# stm32f103core.net
KiCad netlist of a schematic drawn in Altium Designer
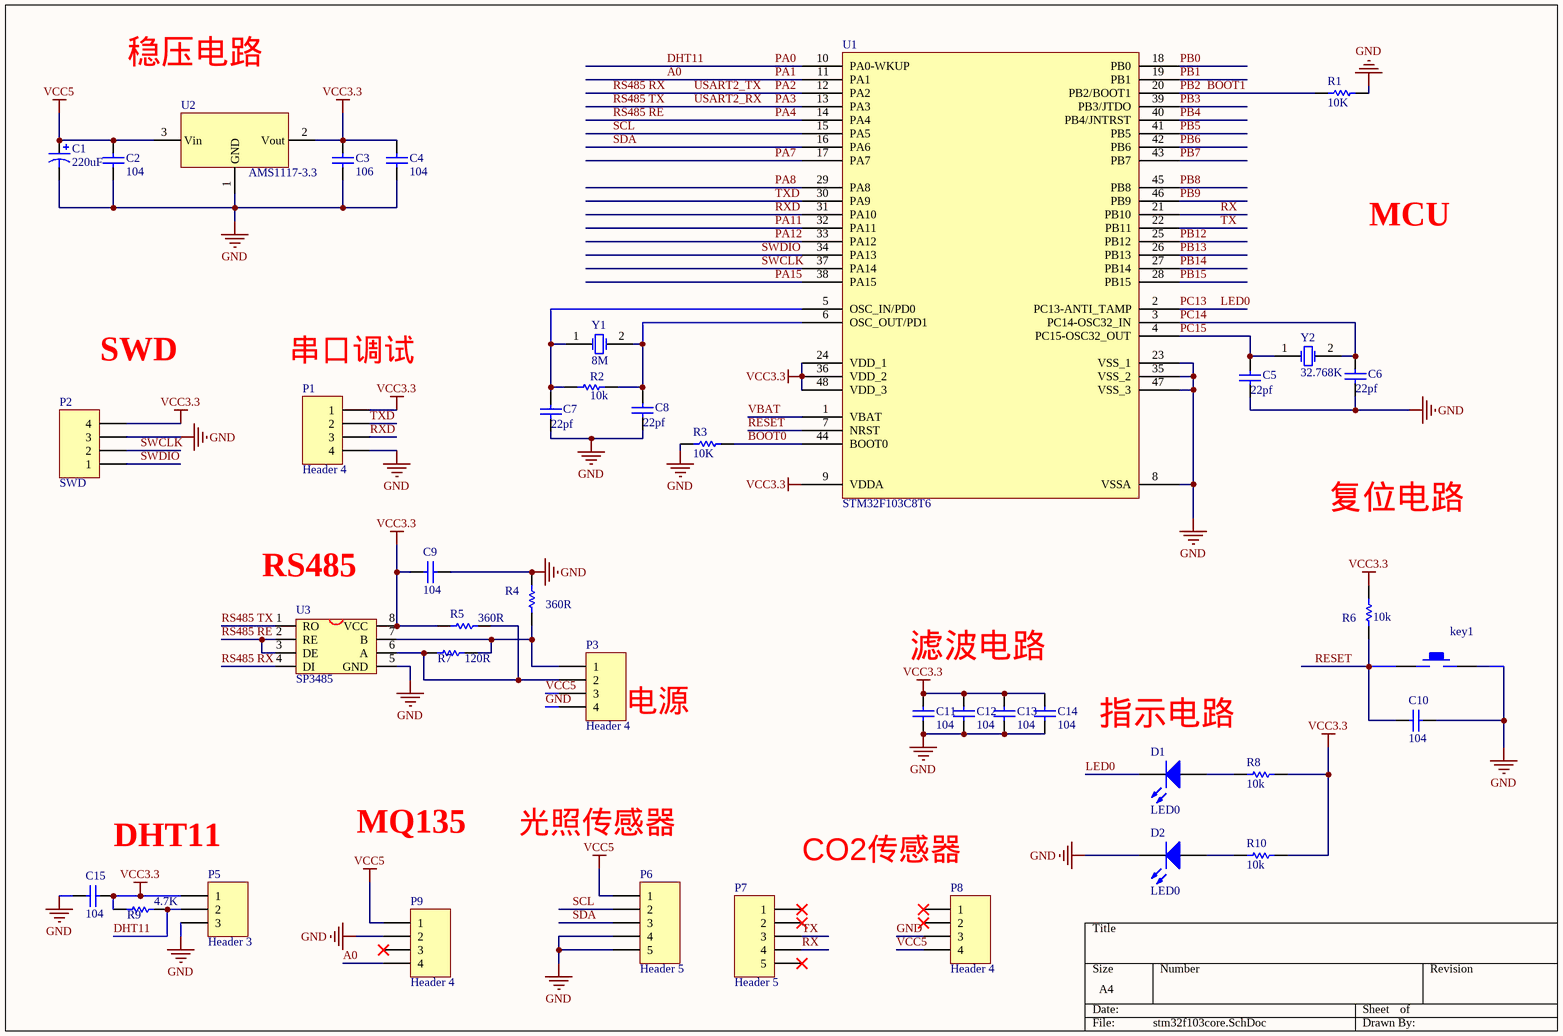
[diagram p0: stm32f103core.SchDoc]

(export (version "E")
  (design (tool "Eeschema 10.0.6"))
  (components
    (comp (ref "C1")
      (value "220uF")
      (footprint "CC6.56.5")
      (description "极性电容")
      (fields (field (name "PUBLISHER") "Altium Limited"))
      (libsource (lib "stm32f103core") (part "Cap Pol2"))
    )
    (comp (ref "C2")
      (value "104")
      (footprint "0603p")
      (description "Capacitor")
      (fields (field (name "PUBLISHER") "Altium Limited"))
      (libsource (lib "stm32f103core") (part "C"))
    )
    (comp (ref "C3")
      (value "106")
      (footprint "0603p")
      (description "Capacitor")
      (fields (field (name "PUBLISHER") "Altium Limited"))
      (libsource (lib "stm32f103core") (part "C"))
    )
    (comp (ref "C4")
      (value "104")
      (footprint "0603p")
      (description "Capacitor")
      (fields (field (name "PUBLISHER") "Altium Limited"))
      (libsource (lib "stm32f103core") (part "C"))
    )
    (comp (ref "C5")
      (value "22pf")
      (footprint "0603p")
      (description "Capacitor")
      (fields (field (name "PUBLISHER") "Altium Limited"))
      (libsource (lib "stm32f103core") (part "C"))
    )
    (comp (ref "C6")
      (value "22pf")
      (footprint "0603p")
      (description "Capacitor")
      (fields (field (name "PUBLISHER") "Altium Limited"))
      (libsource (lib "stm32f103core") (part "C"))
    )
    (comp (ref "C7")
      (value "22pf")
      (footprint "0603p")
      (description "Capacitor")
      (fields (field (name "PUBLISHER") "Altium Limited"))
      (libsource (lib "stm32f103core") (part "C"))
    )
    (comp (ref "C8")
      (value "22pf")
      (footprint "0603p")
      (description "Capacitor")
      (fields (field (name "PUBLISHER") "Altium Limited"))
      (libsource (lib "stm32f103core") (part "C"))
    )
    (comp (ref "C9")
      (value "104")
      (footprint "0603P")
      (description "Capacitor")
      (fields (field (name "PUBLISHER") "Altium Limited"))
      (libsource (lib "stm32f103core") (part "C"))
    )
    (comp (ref "C10")
      (value "104")
      (footprint "0603p")
      (description "Capacitor")
      (fields (field (name "PUBLISHER") "Altium Limited"))
      (libsource (lib "stm32f103core") (part "C"))
    )
    (comp (ref "C11")
      (value "104")
      (footprint "0603p")
      (description "Capacitor")
      (fields (field (name "PUBLISHER") "Altium Limited"))
      (libsource (lib "stm32f103core") (part "C"))
    )
    (comp (ref "C12")
      (value "104")
      (footprint "0603p")
      (description "Capacitor")
      (fields (field (name "PUBLISHER") "Altium Limited"))
      (libsource (lib "stm32f103core") (part "C"))
    )
    (comp (ref "C13")
      (value "104")
      (footprint "0603p")
      (description "Capacitor")
      (fields (field (name "PUBLISHER") "Altium Limited"))
      (libsource (lib "stm32f103core") (part "C"))
    )
    (comp (ref "C14")
      (value "104")
      (footprint "0603p")
      (description "Capacitor")
      (fields (field (name "PUBLISHER") "Altium Limited"))
      (libsource (lib "stm32f103core") (part "C"))
    )
    (comp (ref "C15")
      (value "104")
      (footprint "0603p")
      (description "Capacitor")
      (fields (field (name "PUBLISHER") "Altium Limited"))
      (libsource (lib "stm32f103core") (part "C"))
    )
    (comp (ref "D1")
      (value "LED0")
      (footprint "LED0805")
      (description "Typical INFRARED GaAs LED")
      (fields (field (name "PUBLISHER") "Altium Limited"))
      (libsource (lib "stm32f103core") (part "LED0"))
    )
    (comp (ref "D2")
      (value "LED0")
      (footprint "LED0805")
      (description "Typical INFRARED GaAs LED")
      (fields (field (name "PUBLISHER") "Altium Limited"))
      (libsource (lib "stm32f103core") (part "LED0"))
    )
    (comp (ref "key1") (value "Key") (footprint "Key") (libsource (lib "stm32f103core") (part "Key")))
    (comp (ref "P1")
      (value "Header 4")
      (footprint "HDR1X4")
      (description "Header, 4-Pin")
      (fields (field (name "PUBLISHER") "Altium Limited"))
      (libsource (lib "") (part "Header 4_2"))
    )
    (comp (ref "P2")
      (value "SWD")
      (footprint "HDR1X4")
      (description "Header, 4-Pin")
      (fields (field (name "PUBLISHER") "Altium Limited"))
      (libsource (lib "") (part "Header 4_1"))
    )
    (comp (ref "P3")
      (value "Header 4")
      (footprint "HDR1X4")
      (description "Header, 4-Pin")
      (fields (field (name "PUBLISHER") "Altium Limited"))
      (libsource (lib "Miscellaneous Connectors") (part "Header 4"))
    )
    (comp (ref "P5")
      (value "Header 3")
      (footprint "HDR1X3")
      (description "Header, 3-Pin")
      (fields (field (name "PUBLISHER") "Altium Limited"))
      (libsource (lib "Miscellaneous Connectors") (part "Header 3"))
    )
    (comp (ref "P6")
      (value "Header 5")
      (footprint "HDR1X5")
      (description "Header, 5-Pin")
      (fields (field (name "PUBLISHER") "Altium Limited"))
      (libsource (lib "Miscellaneous Connectors") (part "Header 5"))
    )
    (comp (ref "P7")
      (value "Header 5")
      (footprint "HDR1X5")
      (description "Header, 5-Pin")
      (fields (field (name "PUBLISHER") "Altium Limited"))
      (libsource (lib "") (part "Header 5_1"))
    )
    (comp (ref "P8")
      (value "Header 4")
      (footprint "HDR1X4")
      (description "Header, 4-Pin")
      (fields (field (name "PUBLISHER") "Altium Limited"))
      (libsource (lib "Miscellaneous Connectors") (part "Header 4"))
    )
    (comp (ref "P9")
      (value "Header 4")
      (footprint "HDR1X4")
      (description "Header, 4-Pin")
      (fields (field (name "PUBLISHER") "Altium Limited"))
      (libsource (lib "Miscellaneous Connectors") (part "Header 4"))
    )
    (comp (ref "R1")
      (value "10K")
      (footprint "0603p")
      (description "Resistor")
      (fields (field (name "PUBLISHER") "Altium Limited"))
      (libsource (lib "stm32f103core") (part "R"))
    )
    (comp (ref "R2")
      (value "10k")
      (footprint "0603p")
      (description "Resistor")
      (fields (field (name "PUBLISHER") "Altium Limited"))
      (libsource (lib "stm32f103core") (part "R"))
    )
    (comp (ref "R3")
      (value "10K")
      (footprint "0603p")
      (description "Resistor")
      (fields (field (name "PUBLISHER") "Altium Limited"))
      (libsource (lib "stm32f103core") (part "R"))
    )
    (comp (ref "R4")
      (value "360R")
      (footprint "0603p")
      (description "Resistor")
      (fields (field (name "PUBLISHER") "Altium Limited"))
      (libsource (lib "stm32f103core") (part "R"))
    )
    (comp (ref "R5")
      (value "360R")
      (footprint "0603p")
      (description "Resistor")
      (fields (field (name "PUBLISHER") "Altium Limited"))
      (libsource (lib "stm32f103core") (part "R"))
    )
    (comp (ref "R6")
      (value "10k")
      (footprint "0603p")
      (description "Resistor")
      (fields (field (name "PUBLISHER") "Altium Limited"))
      (libsource (lib "stm32f103core") (part "R"))
    )
    (comp (ref "R7")
      (value "120R")
      (footprint "0603p")
      (description "Resistor")
      (fields (field (name "PUBLISHER") "Altium Limited"))
      (libsource (lib "stm32f103core") (part "R"))
    )
    (comp (ref "R8")
      (value "10k")
      (footprint "0603p")
      (description "Resistor")
      (fields (field (name "PUBLISHER") "Altium Limited"))
      (libsource (lib "stm32f103core") (part "R"))
    )
    (comp (ref "R9")
      (value "4.7K")
      (footprint "0603p")
      (description "Resistor")
      (fields (field (name "PUBLISHER") "Altium Limited"))
      (libsource (lib "stm32f103core") (part "R"))
    )
    (comp (ref "R10")
      (value "10k")
      (footprint "0603p")
      (description "Resistor")
      (fields (field (name "PUBLISHER") "Altium Limited"))
      (libsource (lib "stm32f103core") (part "R"))
    )
    (comp (ref "U1")
      (value "STM32F103C8T6")
      (footprint "LQFP48")
      (libsource (lib "stm32f103core") (part "STM32F103C8T6"))
    )
    (comp (ref "U2")
      (value "AMS1117-3.3")
      (footprint "AMS1117")
      (libsource (lib "stm32f103core") (part "AMS1117"))
    )
    (comp (ref "U3")
      (value "SP3485")
      (footprint "SOP-8")
      (libsource (lib "WarShip V3 STM32103封装库") (part "MAX3485"))
    )
    (comp (ref "Y1")
      (value "8M")
      (footprint "49SMD")
      (description "Crystal Oscillator")
      (fields (field (name "PUBLISHER") "Altium Limited"))
      (libsource (lib "stm32f103core") (part "XTAL"))
    )
    (comp (ref "Y2")
      (value "32.768K")
      (footprint "XTAL32")
      (description "Crystal Oscillator")
      (fields (field (name "PUBLISHER") "Altium Limited"))
      (libsource (lib "stm32f103core") (part "XTAL"))
    )
  )
  (nets
    (net (code "1") (name "/A0") (class "Default")
      (node (ref "P9") (pin "4") (pinfunction "4_4") (pintype "passive"))
      (node (ref "U1") (pin "11") (pinfunction "PA1_11") (pintype "passive"))
    )
    (net (code "2") (name "/BOOT0") (class "Default")
      (node (ref "R3") (pin "2") (pinfunction "2_2") (pintype "passive"))
      (node (ref "U1") (pin "44") (pinfunction "BOOT0_44") (pintype "passive"))
    )
    (net (code "3") (name "/BOOT1") (class "Default")
      (node (ref "R1") (pin "2") (pinfunction "2_2") (pintype "passive"))
      (node (ref "U1") (pin "20") (pinfunction "PB2/BOOT1_20") (pintype "passive"))
    )
    (net (code "4") (name "/DHT11") (class "Default")
      (node (ref "P5") (pin "2") (pinfunction "2_2") (pintype "passive"))
      (node (ref "R9") (pin "2") (pinfunction "2_2") (pintype "passive"))
      (node (ref "U1") (pin "10") (pinfunction "PA0-WKUP_10") (pintype "passive"))
    )
    (net (code "5") (name "/LED0") (class "Default")
      (node (ref "D1") (pin "2") (pinfunction "K_2") (pintype "passive"))
      (node (ref "U1") (pin "2") (pinfunction "PC13-ANTI_TAMP_2") (pintype "passive"))
    )
    (net (code "6") (name "/PA2") (class "Default")
      (node (ref "U1") (pin "12") (pinfunction "PA2_12") (pintype "passive"))
      (node (ref "U3") (pin "4") (pinfunction "DI_4") (pintype "passive"))
    )
    (net (code "7") (name "/PA3") (class "Default")
      (node (ref "U1") (pin "13") (pinfunction "PA3_13") (pintype "passive"))
      (node (ref "U3") (pin "1") (pinfunction "RO_1") (pintype "passive"))
    )
    (net (code "8") (name "/PA4") (class "Default")
      (node (ref "U1") (pin "14") (pinfunction "PA4_14") (pintype "passive"))
      (node (ref "U3") (pin "2") (pinfunction "RE_2") (pintype "passive"))
      (node (ref "U3") (pin "3") (pinfunction "DE_3") (pintype "passive"))
    )
    (net (code "9") (name "/PA7") (class "Default")
      (node (ref "U1") (pin "17") (pinfunction "PA7_17") (pintype "passive"))
    )
    (net (code "10") (name "/PA8") (class "Default")
      (node (ref "U1") (pin "29") (pinfunction "PA8_29") (pintype "passive"))
    )
    (net (code "11") (name "/PA11") (class "Default")
      (node (ref "U1") (pin "32") (pinfunction "PA11_32") (pintype "passive"))
    )
    (net (code "12") (name "/PA12") (class "Default")
      (node (ref "U1") (pin "33") (pinfunction "PA12_33") (pintype "passive"))
    )
    (net (code "13") (name "/PA15") (class "Default")
      (node (ref "U1") (pin "38") (pinfunction "PA15_38") (pintype "passive"))
    )
    (net (code "14") (name "/PB0") (class "Default")
      (node (ref "U1") (pin "18") (pinfunction "PB0_18") (pintype "passive"))
    )
    (net (code "15") (name "/PB1") (class "Default")
      (node (ref "U1") (pin "19") (pinfunction "PB1_19") (pintype "passive"))
    )
    (net (code "16") (name "/PB3") (class "Default")
      (node (ref "U1") (pin "39") (pinfunction "PB3/JTDO_39") (pintype "passive"))
    )
    (net (code "17") (name "/PB4") (class "Default")
      (node (ref "U1") (pin "40") (pinfunction "PB4/JNTRST_40") (pintype "passive"))
    )
    (net (code "18") (name "/PB5") (class "Default")
      (node (ref "U1") (pin "41") (pinfunction "PB5_41") (pintype "passive"))
    )
    (net (code "19") (name "/PB6") (class "Default")
      (node (ref "U1") (pin "42") (pinfunction "PB6_42") (pintype "passive"))
    )
    (net (code "20") (name "/PB7") (class "Default")
      (node (ref "U1") (pin "43") (pinfunction "PB7_43") (pintype "passive"))
    )
    (net (code "21") (name "/PB8") (class "Default")
      (node (ref "U1") (pin "45") (pinfunction "PB8_45") (pintype "passive"))
    )
    (net (code "22") (name "/PB9") (class "Default")
      (node (ref "U1") (pin "46") (pinfunction "PB9_46") (pintype "passive"))
    )
    (net (code "23") (name "/PB12") (class "Default")
      (node (ref "U1") (pin "25") (pinfunction "PB12_25") (pintype "passive"))
    )
    (net (code "24") (name "/PB13") (class "Default")
      (node (ref "U1") (pin "26") (pinfunction "PB13_26") (pintype "passive"))
    )
    (net (code "25") (name "/PB14") (class "Default")
      (node (ref "U1") (pin "27") (pinfunction "PB14_27") (pintype "passive"))
    )
    (net (code "26") (name "/PB15") (class "Default")
      (node (ref "U1") (pin "28") (pinfunction "PB15_28") (pintype "passive"))
    )
    (net (code "27") (name "/PC14") (class "Default")
      (node (ref "C6") (pin "2") (pinfunction "2_2") (pintype "passive"))
      (node (ref "U1") (pin "3") (pinfunction "PC14-OSC32_IN_3") (pintype "passive"))
      (node (ref "Y2") (pin "2") (pinfunction "OSC2_2") (pintype "passive"))
    )
    (net (code "28") (name "/PC15") (class "Default")
      (node (ref "C5") (pin "2") (pinfunction "2_2") (pintype "passive"))
      (node (ref "U1") (pin "4") (pinfunction "PC15-OSC32_OUT_4") (pintype "passive"))
      (node (ref "Y2") (pin "1") (pinfunction "OSC1_1") (pintype "passive"))
    )
    (net (code "29") (name "/RESET") (class "Default")
      (node (ref "C10") (pin "1") (pinfunction "1_1") (pintype "passive"))
      (node (ref "R6") (pin "1") (pinfunction "1_1") (pintype "passive"))
      (node (ref "U1") (pin "7") (pinfunction "NRST_7") (pintype "passive"))
      (node (ref "key1") (pin "1") (pinfunction "1_1") (pintype "passive"))
    )
    (net (code "30") (name "/RX") (class "Default")
      (node (ref "P7") (pin "4") (pinfunction "4_4") (pintype "passive"))
      (node (ref "U1") (pin "21") (pinfunction "PB10_21") (pintype "passive"))
    )
    (net (code "31") (name "/RXD") (class "Default")
      (node (ref "P1") (pin "3") (pinfunction "3_3") (pintype "passive"))
      (node (ref "U1") (pin "31") (pinfunction "PA10_31") (pintype "passive"))
    )
    (net (code "32") (name "/SCL") (class "Default")
      (node (ref "P6") (pin "2") (pinfunction "2_2") (pintype "passive"))
      (node (ref "U1") (pin "15") (pinfunction "PA5_15") (pintype "passive"))
    )
    (net (code "33") (name "/SDA") (class "Default")
      (node (ref "P6") (pin "3") (pinfunction "3_3") (pintype "passive"))
      (node (ref "U1") (pin "16") (pinfunction "PA6_16") (pintype "passive"))
    )
    (net (code "34") (name "/SWCLK") (class "Default")
      (node (ref "P2") (pin "2") (pinfunction "2_2") (pintype "passive"))
      (node (ref "U1") (pin "37") (pinfunction "PA14_37") (pintype "passive"))
    )
    (net (code "35") (name "/SWDIO") (class "Default")
      (node (ref "P2") (pin "1") (pinfunction "1_1") (pintype "passive"))
      (node (ref "U1") (pin "34") (pinfunction "PA13_34") (pintype "passive"))
    )
    (net (code "36") (name "/TX") (class "Default")
      (node (ref "P7") (pin "3") (pinfunction "3_3") (pintype "passive"))
      (node (ref "U1") (pin "22") (pinfunction "PB11_22") (pintype "passive"))
    )
    (net (code "37") (name "/TXD") (class "Default")
      (node (ref "P1") (pin "2") (pinfunction "2_2") (pintype "passive"))
      (node (ref "U1") (pin "30") (pinfunction "PA9_30") (pintype "passive"))
    )
    (net (code "38") (name "/VBAT") (class "Default")
      (node (ref "U1") (pin "1") (pinfunction "VBAT_1") (pintype "passive"))
    )
    (net (code "39") (name "GND") (class "Default")
      (node (ref "C1") (pin "2") (pinfunction "2_2") (pintype "passive"))
      (node (ref "C10") (pin "2") (pinfunction "2_2") (pintype "passive"))
      (node (ref "C11") (pin "1") (pinfunction "1_1") (pintype "passive"))
      (node (ref "C12") (pin "1") (pinfunction "1_1") (pintype "passive"))
      (node (ref "C13") (pin "1") (pinfunction "1_1") (pintype "passive"))
      (node (ref "C14") (pin "1") (pinfunction "1_1") (pintype "passive"))
      (node (ref "C15") (pin "1") (pinfunction "1_1") (pintype "passive"))
      (node (ref "C2") (pin "1") (pinfunction "1_1") (pintype "passive"))
      (node (ref "C3") (pin "1") (pinfunction "1_1") (pintype "passive"))
      (node (ref "C4") (pin "1") (pinfunction "1_1") (pintype "passive"))
      (node (ref "C5") (pin "1") (pinfunction "1_1") (pintype "passive"))
      (node (ref "C6") (pin "1") (pinfunction "1_1") (pintype "passive"))
      (node (ref "C7") (pin "1") (pinfunction "1_1") (pintype "passive"))
      (node (ref "C8") (pin "1") (pinfunction "1_1") (pintype "passive"))
      (node (ref "C9") (pin "2") (pinfunction "2_2") (pintype "passive"))
      (node (ref "D2") (pin "2") (pinfunction "K_2") (pintype "passive"))
      (node (ref "P1") (pin "4") (pinfunction "4_4") (pintype "passive"))
      (node (ref "P2") (pin "3") (pinfunction "3_3") (pintype "passive"))
      (node (ref "P3") (pin "4") (pinfunction "4_4") (pintype "passive"))
      (node (ref "P5") (pin "3") (pinfunction "3_3") (pintype "passive"))
      (node (ref "P6") (pin "4") (pinfunction "4_4") (pintype "passive"))
      (node (ref "P6") (pin "5") (pinfunction "5_5") (pintype "passive"))
      (node (ref "P8") (pin "3") (pinfunction "3_3") (pintype "passive"))
      (node (ref "P9") (pin "2") (pinfunction "2_2") (pintype "passive"))
      (node (ref "R1") (pin "1") (pinfunction "1_1") (pintype "passive"))
      (node (ref "R3") (pin "1") (pinfunction "1_1") (pintype "passive"))
      (node (ref "R4") (pin "2") (pinfunction "2_2") (pintype "passive"))
      (node (ref "U1") (pin "23") (pinfunction "VSS_1_23") (pintype "passive"))
      (node (ref "U1") (pin "35") (pinfunction "VSS_2_35") (pintype "passive"))
      (node (ref "U1") (pin "47") (pinfunction "VSS_3_47") (pintype "passive"))
      (node (ref "U1") (pin "8") (pinfunction "VSSA_8") (pintype "passive"))
      (node (ref "U2") (pin "1") (pinfunction "GND_1") (pintype "passive"))
      (node (ref "U3") (pin "5") (pinfunction "GND_5") (pintype "passive"))
      (node (ref "key1") (pin "2") (pinfunction "2_2") (pintype "passive"))
    )
    (net (code "40") (name "Net-(D1-A)") (class "Default")
      (node (ref "D1") (pin "1") (pinfunction "A_1") (pintype "passive"))
      (node (ref "R8") (pin "1") (pinfunction "1_1") (pintype "passive"))
    )
    (net (code "41") (name "Net-(D2-A)") (class "Default")
      (node (ref "D2") (pin "1") (pinfunction "A_1") (pintype "passive"))
      (node (ref "R10") (pin "1") (pinfunction "1_1") (pintype "passive"))
    )
    (net (code "42") (name "Net-(U1-OSC_IN{slash}PD0)") (class "Default")
      (node (ref "C7") (pin "2") (pinfunction "2_2") (pintype "passive"))
      (node (ref "R2") (pin "1") (pinfunction "1_1") (pintype "passive"))
      (node (ref "U1") (pin "5") (pinfunction "OSC_IN/PD0_5") (pintype "passive"))
      (node (ref "Y1") (pin "1") (pinfunction "OSC1_1") (pintype "passive"))
    )
    (net (code "43") (name "Net-(U1-OSC_OUT{slash}PD1)") (class "Default")
      (node (ref "C8") (pin "2") (pinfunction "2_2") (pintype "passive"))
      (node (ref "R2") (pin "2") (pinfunction "2_2") (pintype "passive"))
      (node (ref "U1") (pin "6") (pinfunction "OSC_OUT/PD1_6") (pintype "passive"))
      (node (ref "Y1") (pin "2") (pinfunction "OSC2_2") (pintype "passive"))
    )
    (net (code "44") (name "Net-(U3-A)") (class "Default")
      (node (ref "P3") (pin "2") (pinfunction "2_2") (pintype "passive"))
      (node (ref "R5") (pin "2") (pinfunction "2_2") (pintype "passive"))
      (node (ref "R7") (pin "1") (pinfunction "1_1") (pintype "passive"))
      (node (ref "U3") (pin "6") (pinfunction "A_6") (pintype "passive"))
    )
    (net (code "45") (name "Net-(U3-B)") (class "Default")
      (node (ref "P3") (pin "1") (pinfunction "1_1") (pintype "passive"))
      (node (ref "R4") (pin "1") (pinfunction "1_1") (pintype "passive"))
      (node (ref "R7") (pin "2") (pinfunction "2_2") (pintype "passive"))
      (node (ref "U3") (pin "7") (pinfunction "B_7") (pintype "passive"))
    )
    (net (code "46") (name "VCC3.3") (class "Default")
      (node (ref "C11") (pin "2") (pinfunction "2_2") (pintype "passive"))
      (node (ref "C12") (pin "2") (pinfunction "2_2") (pintype "passive"))
      (node (ref "C13") (pin "2") (pinfunction "2_2") (pintype "passive"))
      (node (ref "C14") (pin "2") (pinfunction "2_2") (pintype "passive"))
      (node (ref "C15") (pin "2") (pinfunction "2_2") (pintype "passive"))
      (node (ref "C3") (pin "2") (pinfunction "2_2") (pintype "passive"))
      (node (ref "C4") (pin "2") (pinfunction "2_2") (pintype "passive"))
      (node (ref "C9") (pin "1") (pinfunction "1_1") (pintype "passive"))
      (node (ref "P1") (pin "1") (pinfunction "1_1") (pintype "passive"))
      (node (ref "P2") (pin "4") (pinfunction "4_4") (pintype "passive"))
      (node (ref "P5") (pin "1") (pinfunction "1_1") (pintype "passive"))
      (node (ref "R10") (pin "2") (pinfunction "2_2") (pintype "passive"))
      (node (ref "R5") (pin "1") (pinfunction "1_1") (pintype "passive"))
      (node (ref "R6") (pin "2") (pinfunction "2_2") (pintype "passive"))
      (node (ref "R8") (pin "2") (pinfunction "2_2") (pintype "passive"))
      (node (ref "R9") (pin "1") (pinfunction "1_1") (pintype "passive"))
      (node (ref "U1") (pin "24") (pinfunction "VDD_1_24") (pintype "passive"))
      (node (ref "U1") (pin "36") (pinfunction "VDD_2_36") (pintype "passive"))
      (node (ref "U1") (pin "48") (pinfunction "VDD_3_48") (pintype "passive"))
      (node (ref "U1") (pin "9") (pinfunction "VDDA_9") (pintype "passive"))
      (node (ref "U2") (pin "2") (pinfunction "Vout_2") (pintype "passive"))
      (node (ref "U3") (pin "8") (pinfunction "VCC_8") (pintype "passive"))
    )
    (net (code "47") (name "VCC5") (class "Default")
      (node (ref "C1") (pin "1") (pinfunction "1_1") (pintype "passive"))
      (node (ref "C2") (pin "2") (pinfunction "2_2") (pintype "passive"))
      (node (ref "P3") (pin "3") (pinfunction "3_3") (pintype "passive"))
      (node (ref "P6") (pin "1") (pinfunction "1_1") (pintype "passive"))
      (node (ref "P8") (pin "4") (pinfunction "4_4") (pintype "passive"))
      (node (ref "P9") (pin "1") (pinfunction "1_1") (pintype "passive"))
      (node (ref "U2") (pin "3") (pinfunction "Vin_3") (pintype "passive"))
    )
    (net (code "48") (name "unconnected-(P7-Pad1)") (class "Default")
      (node (ref "P7") (pin "1") (pinfunction "1_1") (pintype "passive+no_connect"))
    )
    (net (code "49") (name "unconnected-(P7-Pad2)") (class "Default")
      (node (ref "P7") (pin "2") (pinfunction "2_2") (pintype "passive+no_connect"))
    )
    (net (code "50") (name "unconnected-(P7-Pad5)") (class "Default")
      (node (ref "P7") (pin "5") (pinfunction "5_5") (pintype "passive+no_connect"))
    )
    (net (code "51") (name "unconnected-(P8-Pad1)") (class "Default")
      (node (ref "P8") (pin "1") (pinfunction "1_1") (pintype "passive+no_connect"))
    )
    (net (code "52") (name "unconnected-(P8-Pad2)") (class "Default")
      (node (ref "P8") (pin "2") (pinfunction "2_2") (pintype "passive+no_connect"))
    )
    (net (code "53") (name "unconnected-(P9-Pad3)") (class "Default")
      (node (ref "P9") (pin "3") (pinfunction "3_3") (pintype "passive+no_connect"))
    )
  )
)
